# arduino_shield.net
KiCad netlist of a schematic drawn in EAGLE
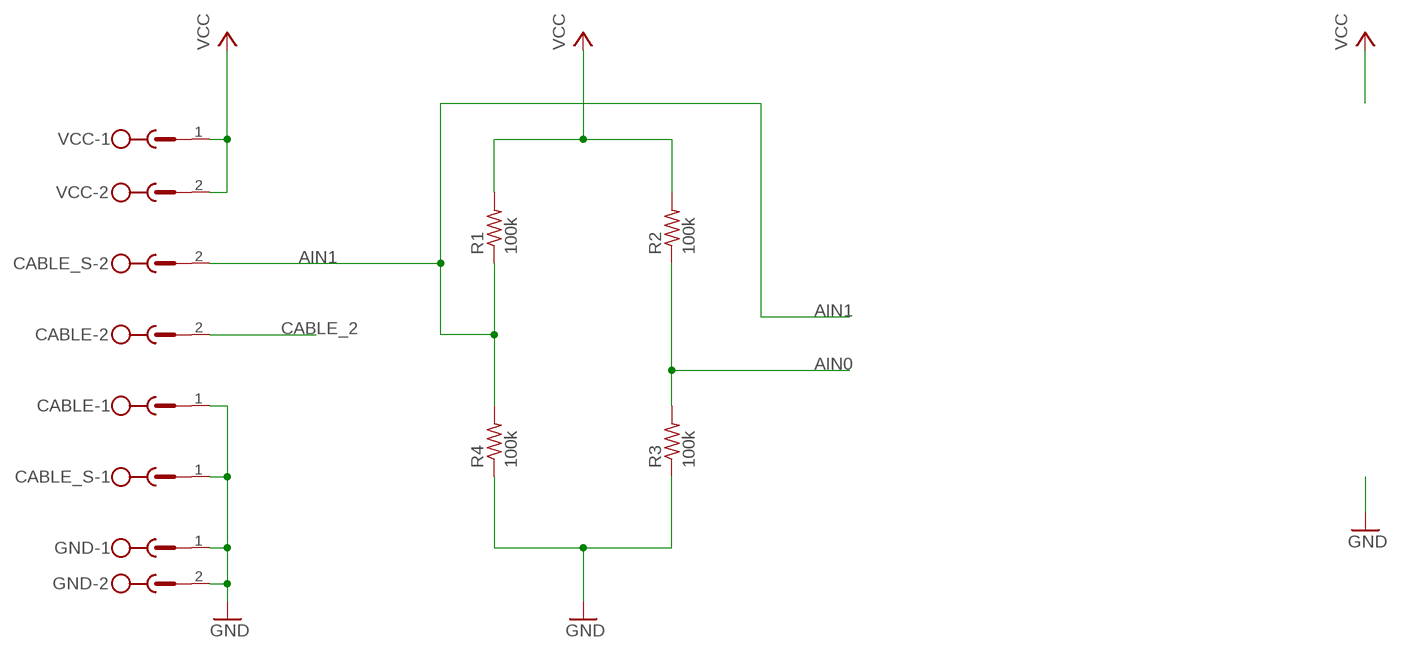
[diagram p0: schematic, sheet 1, part 1 of 2]
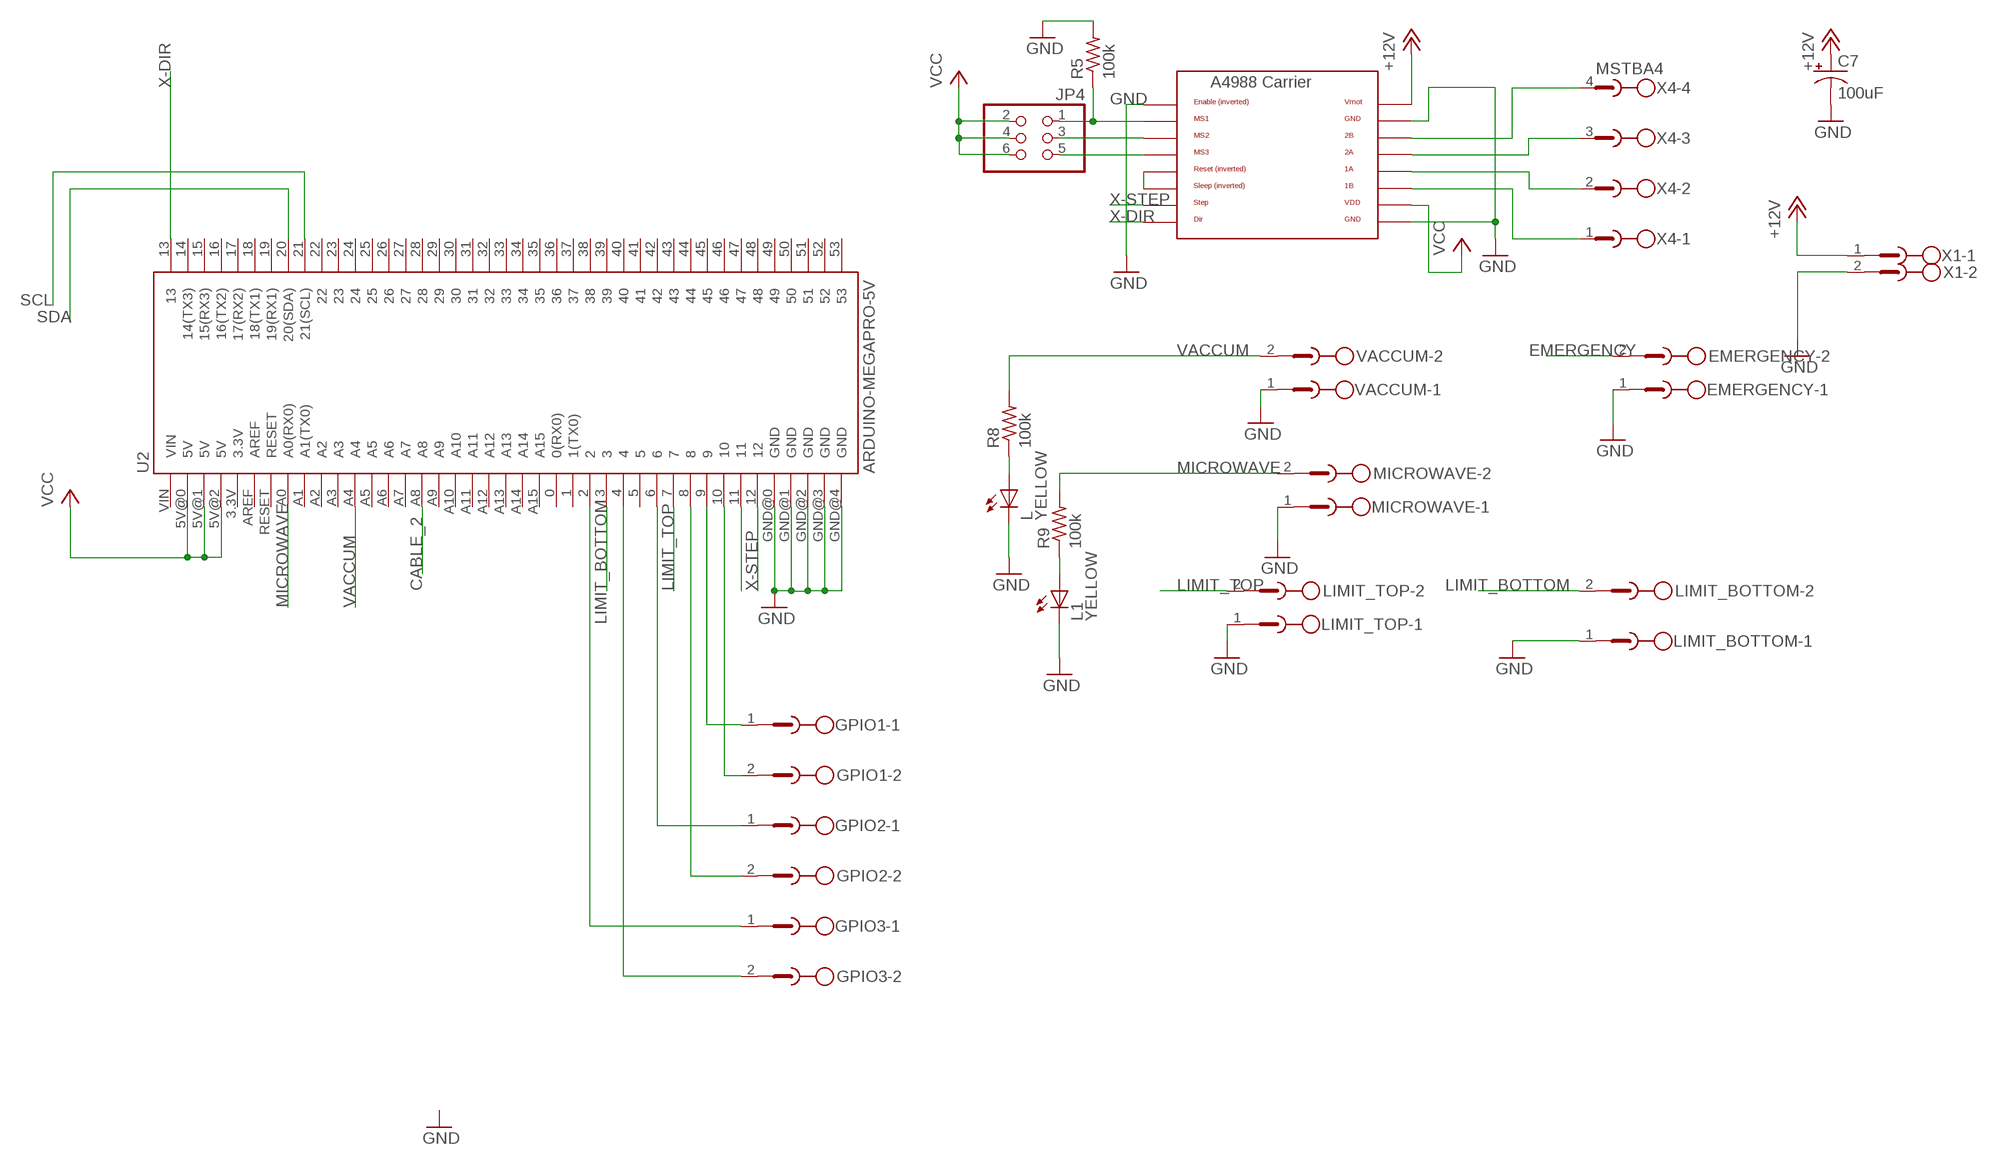
[diagram p1: schematic, sheet 1, part 2 of 2]

(export (version "E")
  (design (tool "Eeschema 10.0.6"))
  (components
    (comp (ref "C7")
      (value "100uF")
      (footprint "eagle-import:153CLV-0605")
      (libsource (lib "eagle-import") (part "CPOL-US153CLV-0605"))
    )
    (comp (ref "CABLE")
      (value "MSTBV2")
      (footprint "eagle-import:MSTBV2")
      (libsource (lib "eagle-import") (part "MSTBV2"))
    )
    (comp (ref "CABLE_S")
      (value "MSTBV2")
      (footprint "eagle-import:MSTBV2")
      (libsource (lib "eagle-import") (part "MSTBV2"))
    )
    (comp (ref "EMERGENCY")
      (value "MSTBV2")
      (footprint "eagle-import:MSTBV2")
      (libsource (lib "eagle-import") (part "MSTBV2"))
    )
    (comp (ref "GND")
      (value "MSTBV2")
      (footprint "eagle-import:MSTBV2")
      (libsource (lib "eagle-import") (part "MSTBV2"))
    )
    (comp (ref "GPIO1")
      (value "MSTBV2")
      (footprint "eagle-import:MSTBV2")
      (libsource (lib "eagle-import") (part "MSTBV2"))
    )
    (comp (ref "GPIO2")
      (value "MSTBV2")
      (footprint "eagle-import:MSTBV2")
      (libsource (lib "eagle-import") (part "MSTBV2"))
    )
    (comp (ref "GPIO3")
      (value "MSTBV2")
      (footprint "eagle-import:MSTBV2")
      (libsource (lib "eagle-import") (part "MSTBV2"))
    )
    (comp (ref "JP4")
      (value "PINHD-2X3")
      (footprint "eagle-import:2X03")
      (libsource (lib "eagle-import") (part "PINHD-2X3"))
    )
    (comp (ref "L")
      (value "YELLOW")
      (footprint "eagle-import:CHIP-LED0805")
      (libsource (lib "eagle-import") (part "LEDCHIP-LED0805"))
    )
    (comp (ref "L1")
      (value "YELLOW")
      (footprint "eagle-import:CHIP-LED0805")
      (libsource (lib "eagle-import") (part "LEDCHIP-LED0805"))
    )
    (comp (ref "LIMIT_BOTTOM")
      (value "MSTBV2")
      (footprint "eagle-import:MSTBV2")
      (libsource (lib "eagle-import") (part "MSTBV2"))
    )
    (comp (ref "LIMIT_TOP")
      (value "MSTBV2")
      (footprint "eagle-import:MSTBV2")
      (libsource (lib "eagle-import") (part "MSTBV2"))
    )
    (comp (ref "MICROWAVE")
      (value "MSTBV2")
      (footprint "eagle-import:MSTBV2")
      (libsource (lib "eagle-import") (part "MSTBV2"))
    )
    (comp (ref "R1")
      (value "100k")
      (footprint "eagle-import:R0805")
      (libsource (lib "eagle-import") (part "R-US_R0805"))
    )
    (comp (ref "R2")
      (value "100k")
      (footprint "eagle-import:R0805")
      (libsource (lib "eagle-import") (part "R-US_R0805"))
    )
    (comp (ref "R3")
      (value "100k")
      (footprint "eagle-import:R0805")
      (libsource (lib "eagle-import") (part "R-US_R0805"))
    )
    (comp (ref "R4")
      (value "100k")
      (footprint "eagle-import:R0805")
      (libsource (lib "eagle-import") (part "R-US_R0805"))
    )
    (comp (ref "R5")
      (value "100k")
      (footprint "eagle-import:R0805")
      (libsource (lib "eagle-import") (part "R-US_R0805"))
    )
    (comp (ref "R8")
      (value "100k")
      (footprint "eagle-import:R0805")
      (libsource (lib "eagle-import") (part "R-US_R0805"))
    )
    (comp (ref "R9")
      (value "100k")
      (footprint "eagle-import:R0805")
      (libsource (lib "eagle-import") (part "R-US_R0805"))
    )
    (comp (ref "U$6")
      (value "A4988BREAKOUT")
      (footprint "eagle-import:A4988BREAKOUT")
      (libsource (lib "eagle-import") (part "A4988BREAKOUT"))
    )
    (comp (ref "U2")
      (value "ARDUINO-MEGAPRO-5V")
      (footprint "eagle-import:ARDUINO_MEGA-PRO-5V")
      (libsource (lib "eagle-import") (part "ARDUINO-MEGAPRO-5V"))
    )
    (comp (ref "VACCUM")
      (value "MSTBV2")
      (footprint "eagle-import:MSTBV2")
      (libsource (lib "eagle-import") (part "MSTBV2"))
    )
    (comp (ref "VCC")
      (value "MSTBV2")
      (footprint "eagle-import:MSTBV2")
      (libsource (lib "eagle-import") (part "MSTBV2"))
    )
    (comp (ref "X1")
      (value "MSTBV2")
      (footprint "eagle-import:MSTBV2")
      (libsource (lib "eagle-import") (part "MSTBV2"))
    )
    (comp (ref "X4")
      (value "MSTBA4")
      (footprint "eagle-import:MSTBA4")
      (libsource (lib "eagle-import") (part "MSTBA4"))
    )
  )
  (nets
    (net (code "1") (name "+12V") (class "Default")
      (node (ref "C7") (pin "+") (pinfunction "+_+") (pintype "passive"))
      (node (ref "U$6") (pin "VMOT") (pinfunction "VMOT_VMOT") (pintype "power_in"))
      (node (ref "X1") (pin "1") (pinfunction "SK_1") (pintype "passive"))
    )
    (net (code "2") (name "/AIN0") (class "Default")
      (node (ref "R2") (pin "1") (pinfunction "1_1") (pintype "passive"))
      (node (ref "R3") (pin "2") (pinfunction "2_2") (pintype "passive"))
    )
    (net (code "3") (name "/AIN1") (class "Default")
      (node (ref "CABLE_S") (pin "2") (pinfunction "SK_2") (pintype "passive"))
      (node (ref "R1") (pin "1") (pinfunction "1_1") (pintype "passive"))
      (node (ref "R4") (pin "2") (pinfunction "2_2") (pintype "passive"))
    )
    (net (code "4") (name "/CABLE_2") (class "Default")
      (node (ref "CABLE") (pin "2") (pinfunction "SK_2") (pintype "passive"))
      (node (ref "U2") (pin "A8") (pinfunction "A8_A8") (pintype "bidirectional"))
    )
    (net (code "5") (name "/EMERGENCY") (class "Default")
      (node (ref "EMERGENCY") (pin "2") (pinfunction "SK_2") (pintype "passive"))
      (node (ref "U2") (pin "11") (pinfunction "11_11") (pintype "bidirectional"))
    )
    (net (code "6") (name "/LIMIT_BOTTOM") (class "Default")
      (node (ref "LIMIT_BOTTOM") (pin "2") (pinfunction "SK_2") (pintype "passive"))
      (node (ref "U2") (pin "3") (pinfunction "3_3") (pintype "bidirectional"))
    )
    (net (code "7") (name "/LIMIT_TOP") (class "Default")
      (node (ref "LIMIT_TOP") (pin "2") (pinfunction "SK_2") (pintype "passive"))
      (node (ref "U2") (pin "7") (pinfunction "7_7") (pintype "bidirectional"))
    )
    (net (code "8") (name "/MICROWAVE") (class "Default")
      (node (ref "MICROWAVE") (pin "2") (pinfunction "SK_2") (pintype "passive"))
      (node (ref "R9") (pin "2") (pinfunction "2_2") (pintype "passive"))
      (node (ref "U2") (pin "A0") (pinfunction "A0(RX0)_A0") (pintype "bidirectional"))
    )
    (net (code "9") (name "/SCL") (class "Default")
      (node (ref "U2") (pin "21") (pinfunction "21(SCL)_21") (pintype "bidirectional"))
    )
    (net (code "10") (name "/SDA") (class "Default")
      (node (ref "U2") (pin "20") (pinfunction "20(SDA)_20") (pintype "bidirectional"))
    )
    (net (code "11") (name "/VACCUM") (class "Default")
      (node (ref "R8") (pin "2") (pinfunction "2_2") (pintype "passive"))
      (node (ref "U2") (pin "A4") (pinfunction "A4_A4") (pintype "bidirectional"))
      (node (ref "VACCUM") (pin "2") (pinfunction "SK_2") (pintype "passive"))
    )
    (net (code "12") (name "/X-DIR") (class "Default")
      (node (ref "U$6") (pin "DIR") (pinfunction "DIR_DIR") (pintype "input"))
      (node (ref "U2") (pin "13") (pinfunction "13_13") (pintype "bidirectional"))
    )
    (net (code "13") (name "/X-STEP") (class "Default")
      (node (ref "U$6") (pin "STEP") (pinfunction "STEP_STEP") (pintype "input"))
      (node (ref "U2") (pin "12") (pinfunction "12_12") (pintype "bidirectional"))
    )
    (net (code "14") (name "GND") (class "Default")
      (node (ref "C7") (pin "-") (pinfunction "-_-") (pintype "passive"))
      (node (ref "CABLE") (pin "1") (pinfunction "SK_1") (pintype "passive"))
      (node (ref "CABLE_S") (pin "1") (pinfunction "SK_1") (pintype "passive"))
      (node (ref "EMERGENCY") (pin "1") (pinfunction "SK_1") (pintype "passive"))
      (node (ref "GND") (pin "1") (pinfunction "SK_1") (pintype "passive"))
      (node (ref "GND") (pin "2") (pinfunction "SK_2") (pintype "passive"))
      (node (ref "L") (pin "C") (pinfunction "C_C") (pintype "passive"))
      (node (ref "L1") (pin "C") (pinfunction "C_C") (pintype "passive"))
      (node (ref "LIMIT_BOTTOM") (pin "1") (pinfunction "SK_1") (pintype "passive"))
      (node (ref "LIMIT_TOP") (pin "1") (pinfunction "SK_1") (pintype "passive"))
      (node (ref "MICROWAVE") (pin "1") (pinfunction "SK_1") (pintype "passive"))
      (node (ref "R3") (pin "1") (pinfunction "1_1") (pintype "passive"))
      (node (ref "R4") (pin "1") (pinfunction "1_1") (pintype "passive"))
      (node (ref "R5") (pin "2") (pinfunction "2_2") (pintype "passive"))
      (node (ref "U$6") (pin "EN") (pinfunction "EN_EN") (pintype "input"))
      (node (ref "U$6") (pin "GND") (pinfunction "GND_GND") (pintype "power_in"))
      (node (ref "U$6") (pin "GND@0") (pinfunction "GND_GND@0") (pintype "power_in"))
      (node (ref "U2") (pin "GND@0") (pinfunction "GND_GND@0") (pintype "bidirectional"))
      (node (ref "U2") (pin "GND@1") (pinfunction "GND_GND@1") (pintype "bidirectional"))
      (node (ref "U2") (pin "GND@2") (pinfunction "GND_GND@2") (pintype "bidirectional"))
      (node (ref "U2") (pin "GND@3") (pinfunction "GND_GND@3") (pintype "bidirectional"))
      (node (ref "U2") (pin "GND@4") (pinfunction "GND_GND@4") (pintype "bidirectional"))
      (node (ref "VACCUM") (pin "1") (pinfunction "SK_1") (pintype "passive"))
      (node (ref "X1") (pin "2") (pinfunction "SK_2") (pintype "passive"))
    )
    (net (code "15") (name "Net-(GPIO1A-SK)") (class "Default")
      (node (ref "GPIO1") (pin "1") (pinfunction "SK_1") (pintype "passive"))
      (node (ref "U2") (pin "9") (pinfunction "9_9") (pintype "bidirectional"))
    )
    (net (code "16") (name "Net-(GPIO1B-SK)") (class "Default")
      (node (ref "GPIO1") (pin "2") (pinfunction "SK_2") (pintype "passive"))
      (node (ref "U2") (pin "10") (pinfunction "10_10") (pintype "bidirectional"))
    )
    (net (code "17") (name "Net-(GPIO2A-SK)") (class "Default")
      (node (ref "GPIO2") (pin "1") (pinfunction "SK_1") (pintype "passive"))
      (node (ref "U2") (pin "6") (pinfunction "6_6") (pintype "bidirectional"))
    )
    (net (code "18") (name "Net-(GPIO2B-SK)") (class "Default")
      (node (ref "GPIO2") (pin "2") (pinfunction "SK_2") (pintype "passive"))
      (node (ref "U2") (pin "8") (pinfunction "8_8") (pintype "bidirectional"))
    )
    (net (code "19") (name "Net-(GPIO3A-SK)") (class "Default")
      (node (ref "GPIO3") (pin "1") (pinfunction "SK_1") (pintype "passive"))
      (node (ref "U2") (pin "2") (pinfunction "2_2") (pintype "bidirectional"))
    )
    (net (code "20") (name "Net-(GPIO3B-SK)") (class "Default")
      (node (ref "GPIO3") (pin "2") (pinfunction "SK_2") (pintype "passive"))
      (node (ref "U2") (pin "4") (pinfunction "4_4") (pintype "bidirectional"))
    )
    (net (code "21") (name "Net-(JP4-Pad1)") (class "Default")
      (node (ref "JP4") (pin "1") (pinfunction "1_1") (pintype "passive"))
      (node (ref "R5") (pin "1") (pinfunction "1_1") (pintype "passive"))
      (node (ref "U$6") (pin "MS1") (pinfunction "MS1_MS1") (pintype "input"))
    )
    (net (code "22") (name "Net-(JP4-Pad3)") (class "Default")
      (node (ref "JP4") (pin "3") (pinfunction "3_3") (pintype "passive"))
      (node (ref "U$6") (pin "MS2") (pinfunction "MS2_MS2") (pintype "input"))
    )
    (net (code "23") (name "Net-(JP4-Pad5)") (class "Default")
      (node (ref "JP4") (pin "5") (pinfunction "5_5") (pintype "passive"))
      (node (ref "U$6") (pin "MS3") (pinfunction "MS3_MS3") (pintype "input"))
    )
    (net (code "24") (name "Net-(L-PadA)") (class "Default")
      (node (ref "L") (pin "A") (pinfunction "A_A") (pintype "passive"))
      (node (ref "R8") (pin "1") (pinfunction "1_1") (pintype "passive"))
    )
    (net (code "25") (name "Net-(L1-PadA)") (class "Default")
      (node (ref "L1") (pin "A") (pinfunction "A_A") (pintype "passive"))
      (node (ref "R9") (pin "1") (pinfunction "1_1") (pintype "passive"))
    )
    (net (code "26") (name "Net-(U$6-Pad1B)") (class "Default")
      (node (ref "U$6") (pin "1B") (pinfunction "1B_1B") (pintype "output"))
      (node (ref "X4") (pin "1") (pinfunction "1_1") (pintype "passive"))
    )
    (net (code "27") (name "Net-(U$6-SLEEP)") (class "Default")
      (node (ref "U$6") (pin "RST") (pinfunction "RST_RST") (pintype "input"))
      (node (ref "U$6") (pin "SLP") (pinfunction "SLEEP_SLP") (pintype "input"))
    )
    (net (code "28") (name "Net-(X4B-1)") (class "Default")
      (node (ref "U$6") (pin "1A") (pinfunction "1A_1A") (pintype "output"))
      (node (ref "X4") (pin "2") (pinfunction "1_2") (pintype "passive"))
    )
    (net (code "29") (name "Net-(X4C-1)") (class "Default")
      (node (ref "U$6") (pin "2A") (pinfunction "2A_2A") (pintype "output"))
      (node (ref "X4") (pin "3") (pinfunction "1_3") (pintype "passive"))
    )
    (net (code "30") (name "Net-(X4D-1)") (class "Default")
      (node (ref "U$6") (pin "2B") (pinfunction "2B_2B") (pintype "output"))
      (node (ref "X4") (pin "4") (pinfunction "1_4") (pintype "passive"))
    )
    (net (code "31") (name "VCC") (class "Default")
      (node (ref "JP4") (pin "2") (pinfunction "2_2") (pintype "passive"))
      (node (ref "JP4") (pin "4") (pinfunction "4_4") (pintype "passive"))
      (node (ref "JP4") (pin "6") (pinfunction "6_6") (pintype "passive"))
      (node (ref "R1") (pin "2") (pinfunction "2_2") (pintype "passive"))
      (node (ref "R2") (pin "2") (pinfunction "2_2") (pintype "passive"))
      (node (ref "U$6") (pin "VDD") (pinfunction "VDD_VDD") (pintype "power_in"))
      (node (ref "U2") (pin "5V@0") (pinfunction "5V_5V@0") (pintype "bidirectional"))
      (node (ref "U2") (pin "5V@1") (pinfunction "5V_5V@1") (pintype "bidirectional"))
      (node (ref "U2") (pin "5V@2") (pinfunction "5V_5V@2") (pintype "bidirectional"))
      (node (ref "VCC") (pin "1") (pinfunction "SK_1") (pintype "passive"))
      (node (ref "VCC") (pin "2") (pinfunction "SK_2") (pintype "passive"))
    )
    (net (code "32") (name "unconnected-(U2-0(RX0)-Pad0)") (class "Default")
      (node (ref "U2") (pin "0") (pinfunction "0(RX0)_0") (pintype "bidirectional"))
    )
    (net (code "33") (name "unconnected-(U2-1(TX0)-Pad1)") (class "Default")
      (node (ref "U2") (pin "1") (pinfunction "1(TX0)_1") (pintype "bidirectional"))
    )
    (net (code "34") (name "unconnected-(U2-14(TX3)-Pad14)") (class "Default")
      (node (ref "U2") (pin "14") (pinfunction "14(TX3)_14") (pintype "bidirectional"))
    )
    (net (code "35") (name "unconnected-(U2-15(RX3)-Pad15)") (class "Default")
      (node (ref "U2") (pin "15") (pinfunction "15(RX3)_15") (pintype "bidirectional"))
    )
    (net (code "36") (name "unconnected-(U2-16(TX2)-Pad16)") (class "Default")
      (node (ref "U2") (pin "16") (pinfunction "16(TX2)_16") (pintype "bidirectional"))
    )
    (net (code "37") (name "unconnected-(U2-17(RX2)-Pad17)") (class "Default")
      (node (ref "U2") (pin "17") (pinfunction "17(RX2)_17") (pintype "bidirectional"))
    )
    (net (code "38") (name "unconnected-(U2-18(TX1)-Pad18)") (class "Default")
      (node (ref "U2") (pin "18") (pinfunction "18(TX1)_18") (pintype "bidirectional"))
    )
    (net (code "39") (name "unconnected-(U2-19(RX1)-Pad19)") (class "Default")
      (node (ref "U2") (pin "19") (pinfunction "19(RX1)_19") (pintype "bidirectional"))
    )
    (net (code "40") (name "unconnected-(U2-A1(TX0)-PadA1)") (class "Default")
      (node (ref "U2") (pin "A1") (pinfunction "A1(TX0)_A1") (pintype "bidirectional"))
    )
    (net (code "41") (name "unconnected-(U2-Pad3.3V)") (class "Default")
      (node (ref "U2") (pin "3.3V") (pinfunction "3.3V_3.3V") (pintype "bidirectional"))
    )
    (net (code "42") (name "unconnected-(U2-Pad5)") (class "Default")
      (node (ref "U2") (pin "5") (pinfunction "5_5") (pintype "bidirectional"))
    )
    (net (code "43") (name "unconnected-(U2-Pad22)") (class "Default")
      (node (ref "U2") (pin "22") (pinfunction "22_22") (pintype "bidirectional"))
    )
    (net (code "44") (name "unconnected-(U2-Pad23)") (class "Default")
      (node (ref "U2") (pin "23") (pinfunction "23_23") (pintype "bidirectional"))
    )
    (net (code "45") (name "unconnected-(U2-Pad24)") (class "Default")
      (node (ref "U2") (pin "24") (pinfunction "24_24") (pintype "bidirectional"))
    )
    (net (code "46") (name "unconnected-(U2-Pad25)") (class "Default")
      (node (ref "U2") (pin "25") (pinfunction "25_25") (pintype "bidirectional"))
    )
    (net (code "47") (name "unconnected-(U2-Pad26)") (class "Default")
      (node (ref "U2") (pin "26") (pinfunction "26_26") (pintype "bidirectional"))
    )
    (net (code "48") (name "unconnected-(U2-Pad27)") (class "Default")
      (node (ref "U2") (pin "27") (pinfunction "27_27") (pintype "bidirectional"))
    )
    (net (code "49") (name "unconnected-(U2-Pad28)") (class "Default")
      (node (ref "U2") (pin "28") (pinfunction "28_28") (pintype "bidirectional"))
    )
    (net (code "50") (name "unconnected-(U2-Pad29)") (class "Default")
      (node (ref "U2") (pin "29") (pinfunction "29_29") (pintype "bidirectional"))
    )
    (net (code "51") (name "unconnected-(U2-Pad30)") (class "Default")
      (node (ref "U2") (pin "30") (pinfunction "30_30") (pintype "bidirectional"))
    )
    (net (code "52") (name "unconnected-(U2-Pad31)") (class "Default")
      (node (ref "U2") (pin "31") (pinfunction "31_31") (pintype "bidirectional"))
    )
    (net (code "53") (name "unconnected-(U2-Pad32)") (class "Default")
      (node (ref "U2") (pin "32") (pinfunction "32_32") (pintype "bidirectional"))
    )
    (net (code "54") (name "unconnected-(U2-Pad33)") (class "Default")
      (node (ref "U2") (pin "33") (pinfunction "33_33") (pintype "bidirectional"))
    )
    (net (code "55") (name "unconnected-(U2-Pad34)") (class "Default")
      (node (ref "U2") (pin "34") (pinfunction "34_34") (pintype "bidirectional"))
    )
    (net (code "56") (name "unconnected-(U2-Pad35)") (class "Default")
      (node (ref "U2") (pin "35") (pinfunction "35_35") (pintype "bidirectional"))
    )
    (net (code "57") (name "unconnected-(U2-Pad36)") (class "Default")
      (node (ref "U2") (pin "36") (pinfunction "36_36") (pintype "bidirectional"))
    )
    (net (code "58") (name "unconnected-(U2-Pad37)") (class "Default")
      (node (ref "U2") (pin "37") (pinfunction "37_37") (pintype "bidirectional"))
    )
    (net (code "59") (name "unconnected-(U2-Pad38)") (class "Default")
      (node (ref "U2") (pin "38") (pinfunction "38_38") (pintype "bidirectional"))
    )
    (net (code "60") (name "unconnected-(U2-Pad39)") (class "Default")
      (node (ref "U2") (pin "39") (pinfunction "39_39") (pintype "bidirectional"))
    )
    (net (code "61") (name "unconnected-(U2-Pad40)") (class "Default")
      (node (ref "U2") (pin "40") (pinfunction "40_40") (pintype "bidirectional"))
    )
    (net (code "62") (name "unconnected-(U2-Pad41)") (class "Default")
      (node (ref "U2") (pin "41") (pinfunction "41_41") (pintype "bidirectional"))
    )
    (net (code "63") (name "unconnected-(U2-Pad42)") (class "Default")
      (node (ref "U2") (pin "42") (pinfunction "42_42") (pintype "bidirectional"))
    )
    (net (code "64") (name "unconnected-(U2-Pad43)") (class "Default")
      (node (ref "U2") (pin "43") (pinfunction "43_43") (pintype "bidirectional"))
    )
    (net (code "65") (name "unconnected-(U2-Pad44)") (class "Default")
      (node (ref "U2") (pin "44") (pinfunction "44_44") (pintype "bidirectional"))
    )
    (net (code "66") (name "unconnected-(U2-Pad45)") (class "Default")
      (node (ref "U2") (pin "45") (pinfunction "45_45") (pintype "bidirectional"))
    )
    (net (code "67") (name "unconnected-(U2-Pad46)") (class "Default")
      (node (ref "U2") (pin "46") (pinfunction "46_46") (pintype "bidirectional"))
    )
    (net (code "68") (name "unconnected-(U2-Pad47)") (class "Default")
      (node (ref "U2") (pin "47") (pinfunction "47_47") (pintype "bidirectional"))
    )
    (net (code "69") (name "unconnected-(U2-Pad48)") (class "Default")
      (node (ref "U2") (pin "48") (pinfunction "48_48") (pintype "bidirectional"))
    )
    (net (code "70") (name "unconnected-(U2-Pad49)") (class "Default")
      (node (ref "U2") (pin "49") (pinfunction "49_49") (pintype "bidirectional"))
    )
    (net (code "71") (name "unconnected-(U2-Pad50)") (class "Default")
      (node (ref "U2") (pin "50") (pinfunction "50_50") (pintype "bidirectional"))
    )
    (net (code "72") (name "unconnected-(U2-Pad51)") (class "Default")
      (node (ref "U2") (pin "51") (pinfunction "51_51") (pintype "bidirectional"))
    )
    (net (code "73") (name "unconnected-(U2-Pad52)") (class "Default")
      (node (ref "U2") (pin "52") (pinfunction "52_52") (pintype "bidirectional"))
    )
    (net (code "74") (name "unconnected-(U2-Pad53)") (class "Default")
      (node (ref "U2") (pin "53") (pinfunction "53_53") (pintype "bidirectional"))
    )
    (net (code "75") (name "unconnected-(U2-PadA2)") (class "Default")
      (node (ref "U2") (pin "A2") (pinfunction "A2_A2") (pintype "bidirectional"))
    )
    (net (code "76") (name "unconnected-(U2-PadA3)") (class "Default")
      (node (ref "U2") (pin "A3") (pinfunction "A3_A3") (pintype "bidirectional"))
    )
    (net (code "77") (name "unconnected-(U2-PadA5)") (class "Default")
      (node (ref "U2") (pin "A5") (pinfunction "A5_A5") (pintype "bidirectional"))
    )
    (net (code "78") (name "unconnected-(U2-PadA6)") (class "Default")
      (node (ref "U2") (pin "A6") (pinfunction "A6_A6") (pintype "bidirectional"))
    )
    (net (code "79") (name "unconnected-(U2-PadA7)") (class "Default")
      (node (ref "U2") (pin "A7") (pinfunction "A7_A7") (pintype "bidirectional"))
    )
    (net (code "80") (name "unconnected-(U2-PadA9)") (class "Default")
      (node (ref "U2") (pin "A9") (pinfunction "A9_A9") (pintype "bidirectional"))
    )
    (net (code "81") (name "unconnected-(U2-PadA10)") (class "Default")
      (node (ref "U2") (pin "A10") (pinfunction "A10_A10") (pintype "bidirectional"))
    )
    (net (code "82") (name "unconnected-(U2-PadA11)") (class "Default")
      (node (ref "U2") (pin "A11") (pinfunction "A11_A11") (pintype "bidirectional"))
    )
    (net (code "83") (name "unconnected-(U2-PadA12)") (class "Default")
      (node (ref "U2") (pin "A12") (pinfunction "A12_A12") (pintype "bidirectional"))
    )
    (net (code "84") (name "unconnected-(U2-PadA13)") (class "Default")
      (node (ref "U2") (pin "A13") (pinfunction "A13_A13") (pintype "bidirectional"))
    )
    (net (code "85") (name "unconnected-(U2-PadA14)") (class "Default")
      (node (ref "U2") (pin "A14") (pinfunction "A14_A14") (pintype "bidirectional"))
    )
    (net (code "86") (name "unconnected-(U2-PadA15)") (class "Default")
      (node (ref "U2") (pin "A15") (pinfunction "A15_A15") (pintype "bidirectional"))
    )
    (net (code "87") (name "unconnected-(U2-PadAREF)") (class "Default")
      (node (ref "U2") (pin "AREF") (pinfunction "AREF_AREF") (pintype "bidirectional"))
    )
    (net (code "88") (name "unconnected-(U2-PadRESET)") (class "Default")
      (node (ref "U2") (pin "RESET") (pinfunction "RESET_RESET") (pintype "bidirectional"))
    )
    (net (code "89") (name "unconnected-(U2-PadVIN)") (class "Default")
      (node (ref "U2") (pin "VIN") (pinfunction "VIN_VIN") (pintype "bidirectional"))
    )
  )
)
